# StudentForce_MIC.net
KiCad netlist of a schematic drawn in Altium Designer
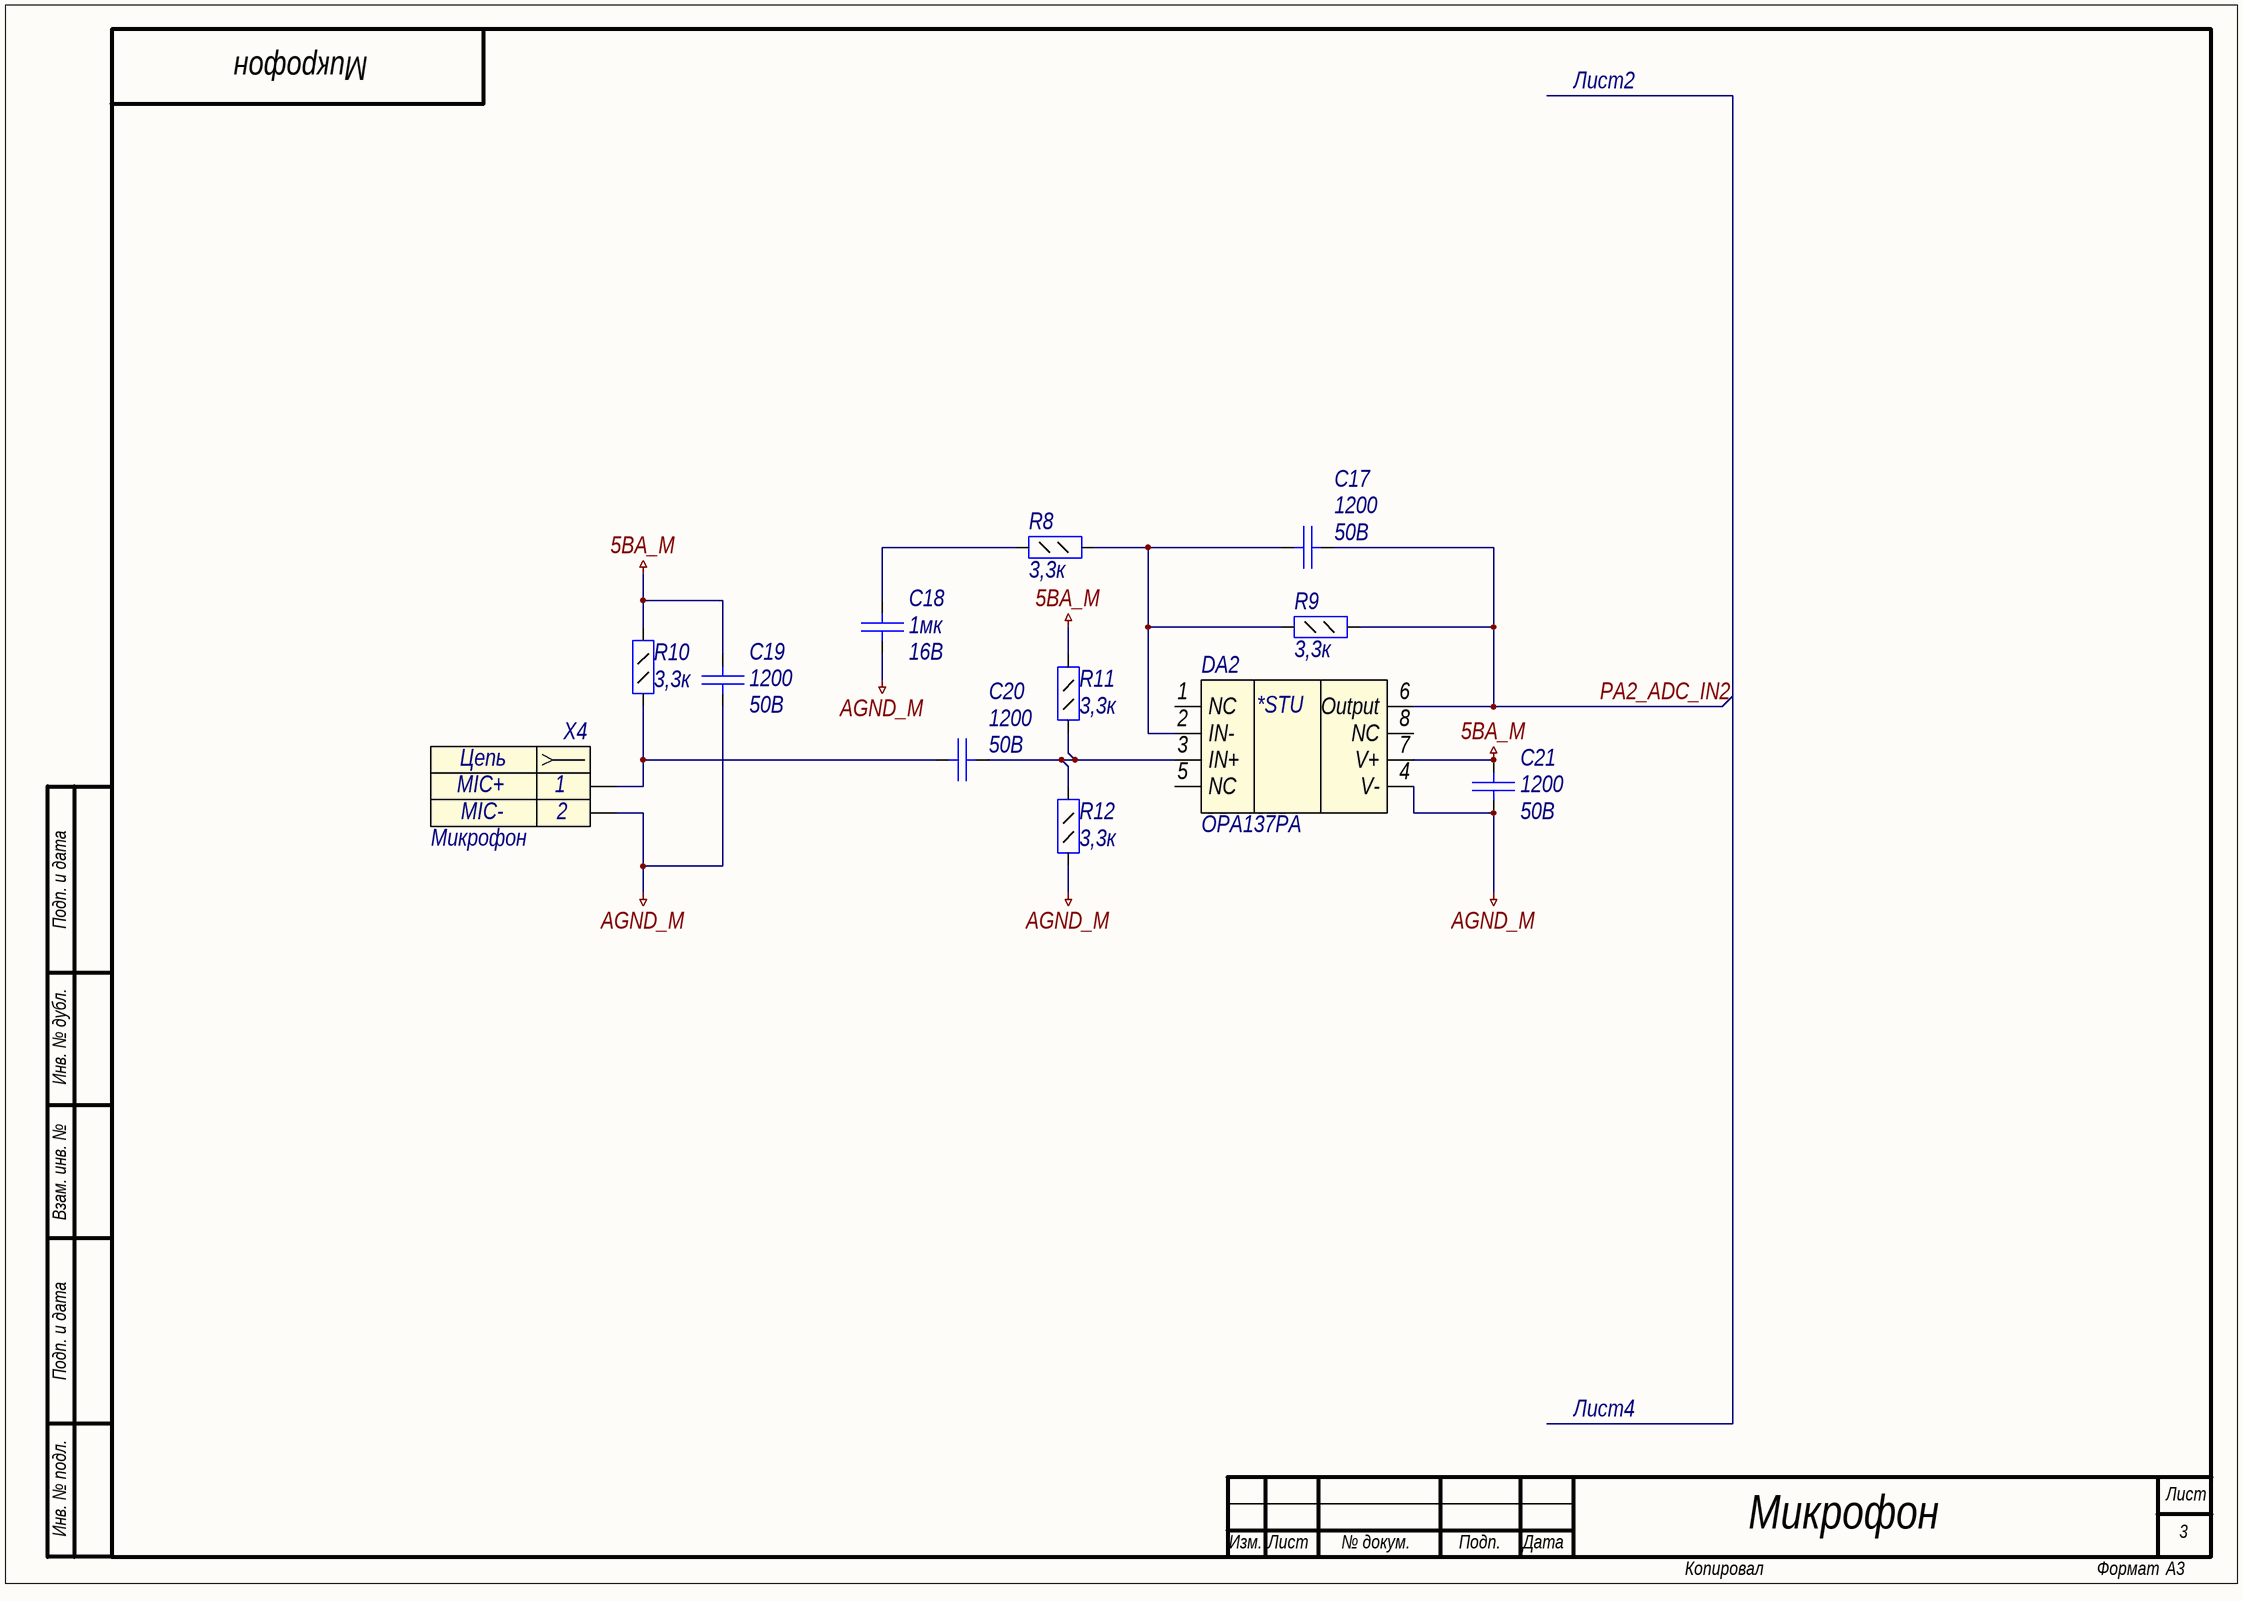
[diagram p0: StudentForce_MIC.SchDoc]

(export (version "E")
  (design (tool "Eeschema 10.0.6"))
  (components
    (comp (ref "C17")
      (value "1200")
      (footprint "C0805")
      (description "Конденсатор")
      (fields
        (field (name "VOLTAGE") "50В")
        (field (name "PART NUMBER") "GRM216R71H122K")
        (field (name "Comment") "Capacitor")
      )
      (libsource (lib "MOP44") (part "Capacitor"))
    )
    (comp (ref "C18")
      (value "1мк")
      (footprint "C0805")
      (description "Конденсатор")
      (fields
        (field (name "VOLTAGE") "16B")
        (field (name "PART NUMBER") "GRM21BR71C105K")
        (field (name "Comment") "Capacitor")
      )
      (libsource (lib "MOP44") (part "Capacitor"))
    )
    (comp (ref "C19")
      (value "1200")
      (footprint "C0805")
      (description "Конденсатор")
      (fields
        (field (name "VOLTAGE") "50В")
        (field (name "PART NUMBER") "GRM216R71H122K")
        (field (name "Comment") "Capacitor")
      )
      (libsource (lib "MOP44") (part "Capacitor"))
    )
    (comp (ref "C20")
      (value "1200")
      (footprint "C0805")
      (description "Конденсатор")
      (fields
        (field (name "VOLTAGE") "50В")
        (field (name "PART NUMBER") "GRM216R71H122K")
        (field (name "Comment") "Capacitor")
      )
      (libsource (lib "MOP44") (part "Capacitor"))
    )
    (comp (ref "C21")
      (value "1200")
      (footprint "C0805")
      (description "Конденсатор")
      (fields
        (field (name "VOLTAGE") "50В")
        (field (name "PART NUMBER") "GRM216R71H122K")
        (field (name "Comment") "Capacitor")
      )
      (libsource (lib "MOP44") (part "Capacitor"))
    )
    (comp (ref "DA2")
      (value "OPA137PA")
      (footprint "DIP8")
      (description "FET-INPUT OPERATIONAL AMPLIFIERS")
      (fields (field (name "PART NUMBER") "OPA137PA"))
      (libsource (lib "MOP44") (part "OPA137PA"))
    )
    (comp (ref "R8")
      (value "3,3к")
      (footprint "R0805")
      (description "Резистор")
      (fields (field (name "POWER") "0,125Вт") (field (name "PART NUMBER") "RC0805FR-072K3"))
      (libsource (lib "") (part "Resistor_0,125Вт_1"))
    )
    (comp (ref "R9")
      (value "3,3к")
      (footprint "R0805")
      (description "Резистор")
      (fields (field (name "POWER") "0,125Вт") (field (name "PART NUMBER") "RC0805FR-072K3"))
      (libsource (lib "") (part "Resistor_0,125Вт_1"))
    )
    (comp (ref "R10")
      (value "3,3к")
      (footprint "R0805")
      (description "Резистор")
      (fields (field (name "POWER") "0,125Вт") (field (name "PART NUMBER") "RC0805FR-072K3"))
      (libsource (lib "MOP44") (part "Resistor_0,125Вт"))
    )
    (comp (ref "R11")
      (value "3,3к")
      (footprint "R0805")
      (description "Резистор")
      (fields (field (name "POWER") "0,125Вт") (field (name "PART NUMBER") "RC0805FR-072K3"))
      (libsource (lib "MOP44") (part "Resistor_0,125Вт"))
    )
    (comp (ref "R12")
      (value "3,3к")
      (footprint "R0805")
      (description "Резистор")
      (fields (field (name "POWER") "0,125Вт") (field (name "PART NUMBER") "RC0805FR-072K3"))
      (libsource (lib "MOP44") (part "Resistor_0,125Вт"))
    )
    (comp (ref "X4")
      (value "Микрофон")
      (footprint "CWF-2R")
      (description "Разъем - 2 конт. розетка")
      (fields (field (name "PART NUMBER") "DS1069-2 MR-A"))
      (libsource (lib "MOP44") (part "Header_2_sct"))
    )
  )
  (nets
    (net (code "1") (name "/PA2_ADC_IN2") (class "Default")
      (node (ref "C17") (pin "1") (pinfunction "1_1") (pintype "passive"))
      (node (ref "DA2") (pin "6") (pinfunction "Output_6") (pintype "power_in"))
      (node (ref "R9") (pin "2") (pinfunction "2_2") (pintype "passive"))
    )
    (net (code "2") (name "5BA_M") (class "Default")
      (node (ref "C19") (pin "1") (pinfunction "1_1") (pintype "passive"))
      (node (ref "C21") (pin "1") (pinfunction "1_1") (pintype "passive"))
      (node (ref "DA2") (pin "7") (pinfunction "V+_7") (pintype "power_in"))
      (node (ref "R10") (pin "2") (pinfunction "2_2") (pintype "passive"))
      (node (ref "R11") (pin "2") (pinfunction "2_2") (pintype "passive"))
    )
    (net (code "3") (name "AGND_M") (class "Default")
      (node (ref "C18") (pin "1") (pinfunction "1_1") (pintype "passive"))
      (node (ref "C19") (pin "2") (pinfunction "2_2") (pintype "passive"))
      (node (ref "C21") (pin "2") (pinfunction "2_2") (pintype "passive"))
      (node (ref "DA2") (pin "4") (pinfunction "V-_4") (pintype "power_in"))
      (node (ref "R12") (pin "1") (pinfunction "1_1") (pintype "passive"))
      (node (ref "X4") (pin "2") (pinfunction "2_2") (pintype "passive"))
    )
    (net (code "4") (name "Net-(C18-Pad2)") (class "Default")
      (node (ref "C18") (pin "2") (pinfunction "2_2") (pintype "passive"))
      (node (ref "R8") (pin "1") (pinfunction "1_1") (pintype "passive"))
    )
    (net (code "5") (name "Net-(C20-Pad2)") (class "Default")
      (node (ref "C20") (pin "2") (pinfunction "2_2") (pintype "passive"))
      (node (ref "R10") (pin "1") (pinfunction "1_1") (pintype "passive"))
      (node (ref "X4") (pin "1") (pinfunction "1_1") (pintype "passive"))
    )
    (net (code "6") (name "Net-(DA2-IN+)") (class "Default")
      (node (ref "C20") (pin "1") (pinfunction "1_1") (pintype "passive"))
      (node (ref "DA2") (pin "3") (pinfunction "IN+_3") (pintype "power_in"))
      (node (ref "R11") (pin "1") (pinfunction "1_1") (pintype "passive"))
      (node (ref "R12") (pin "2") (pinfunction "2_2") (pintype "passive"))
    )
    (net (code "7") (name "Net-(DA2-IN-)") (class "Default")
      (node (ref "C17") (pin "2") (pinfunction "2_2") (pintype "passive"))
      (node (ref "DA2") (pin "2") (pinfunction "IN-_2") (pintype "power_in"))
      (node (ref "R8") (pin "2") (pinfunction "2_2") (pintype "passive"))
      (node (ref "R9") (pin "1") (pinfunction "1_1") (pintype "passive"))
    )
    (net (code "8") (name "unconnected-(DA2-NC-Pad1)") (class "Default")
      (node (ref "DA2") (pin "1") (pinfunction "NC_1") (pintype "power_in"))
    )
    (net (code "9") (name "unconnected-(DA2-NC-Pad5)") (class "Default")
      (node (ref "DA2") (pin "5") (pinfunction "NC_5") (pintype "power_in"))
    )
    (net (code "10") (name "unconnected-(DA2-NC-Pad8)") (class "Default")
      (node (ref "DA2") (pin "8") (pinfunction "NC_8") (pintype "power_in"))
    )
  )
)
